# Domino_Di_No_Teardrop.net
KiCad netlist of a schematic drawn in EAGLE
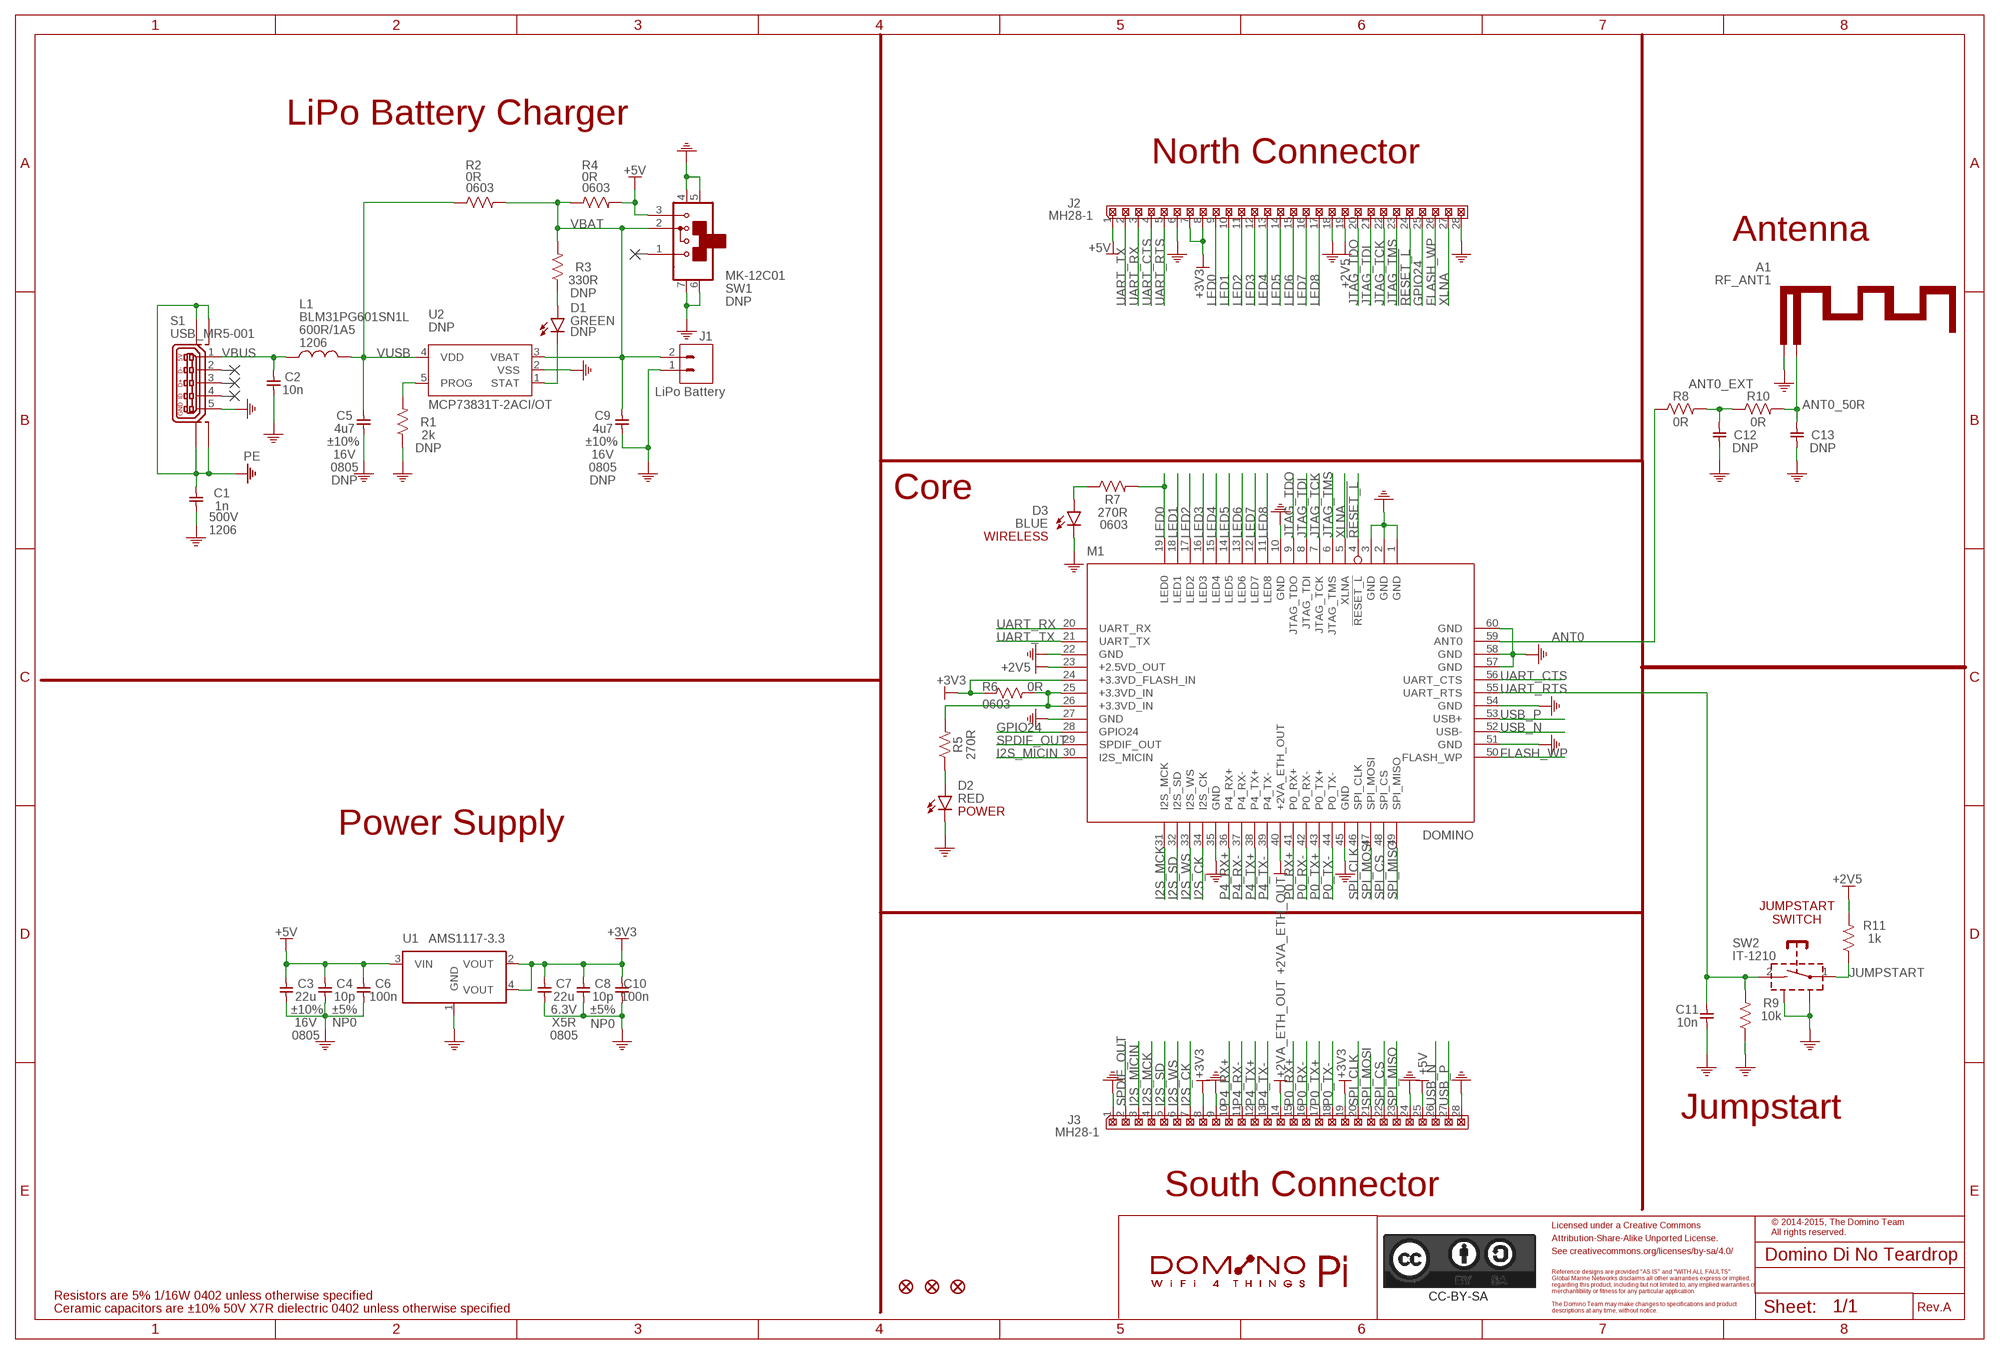
[diagram p0: schematic, sheet 1]

(export (version "E")
  (design (tool "Eeschema 10.0.6"))
  (components
    (comp (ref "A1")
      (value "RF_ANT1")
      (footprint "eagle-import:RF_ANT1")
      (fields (field (name "PARTNO") "WIFI_ANT-2.4GHz"))
      (libsource (lib "eagle-import") (part "RF_ANT1"))
    )
    (comp (ref "C1")
      (value "1n")
      (footprint "eagle-import:C1206")
      (fields
        (field (name "SIZE") "1206")
        (field (name "PARTNO") "C1206_1n_X7R_10%_CER_500V")
        (field (name "VOLT") "500V")
      )
      (libsource (lib "eagle-import") (part "CAP_1206"))
    )
    (comp (ref "C2")
      (value "10n")
      (footprint "eagle-import:C0402")
      (fields (field (name "PARTNO") "C0402_10n_X7R_10%_CER_50V"))
      (libsource (lib "eagle-import") (part "CAP_0402"))
    )
    (comp (ref "C3")
      (value "22u")
      (footprint "eagle-import:C0805")
      (fields
        (field (name "SIZE") "0805")
        (field (name "PARTNO") "C0805_22u_X5R_20%_CER_6V3")
        (field (name "TOL") "±10%")
        (field (name "VOLT") "16V")
      )
      (libsource (lib "eagle-import") (part "CAP_0805"))
    )
    (comp (ref "C4")
      (value "10p")
      (footprint "eagle-import:C0402")
      (fields
        (field (name "PARTNO") "C0402_10p_NP0_5%_CER_50V")
        (field (name "TC") "NP0")
        (field (name "TOL") "±5%")
      )
      (libsource (lib "eagle-import") (part "CAP_0402"))
    )
    (comp (ref "C5")
      (value "4u7")
      (footprint "eagle-import:C0805")
      (fields
        (field (name "SIZE") "0805")
        (field (name "PARTNO") "C0805_4u7_X5R_10%_CER_16V")
        (field (name "TOL") "±10%")
        (field (name "VOLT") "16V")
      )
      (libsource (lib "eagle-import") (part "CAP_0805"))
    )
    (comp (ref "C6")
      (value "100n")
      (footprint "eagle-import:C0402")
      (fields (field (name "PARTNO") "C0402_100n_X7R_10%_CER_50V"))
      (libsource (lib "eagle-import") (part "CAP_0402"))
    )
    (comp (ref "C7")
      (value "22u")
      (footprint "eagle-import:C0805")
      (fields
        (field (name "SIZE") "0805")
        (field (name "PARTNO") "C0805_22u_X5R_20%_CER_6V3")
        (field (name "TC") "X5R")
        (field (name "VOLT") "6.3V")
      )
      (libsource (lib "eagle-import") (part "CAP_0805"))
    )
    (comp (ref "C8")
      (value "10p")
      (footprint "eagle-import:C0402")
      (fields
        (field (name "PARTNO") "C0402_10p_NP0_5%_CER_50V")
        (field (name "TC") "NP0")
        (field (name "TOL") "±5%")
      )
      (libsource (lib "eagle-import") (part "CAP_0402"))
    )
    (comp (ref "C9")
      (value "4u7")
      (footprint "eagle-import:C0805")
      (fields
        (field (name "SIZE") "0805")
        (field (name "PARTNO") "C0805_4u7_X5R_10%_CER_16V")
        (field (name "TOL") "±10%")
        (field (name "VOLT") "16V")
      )
      (libsource (lib "eagle-import") (part "CAP_0805"))
    )
    (comp (ref "C10")
      (value "100n")
      (footprint "eagle-import:C0402")
      (fields (field (name "PARTNO") "C0402_100n_X7R_10%_CER_50V"))
      (libsource (lib "eagle-import") (part "CAP_0402"))
    )
    (comp (ref "C11")
      (value "10n")
      (footprint "eagle-import:C0402")
      (fields (field (name "PARTNO") "C0402_10n_X7R_10%_CER_50V"))
      (libsource (lib "eagle-import") (part "CAP_0402"))
    )
    (comp (ref "C12")
      (value "DNP")
      (footprint "eagle-import:C0402")
      (fields (field (name "PARTNO") "C0402_DNP"))
      (libsource (lib "eagle-import") (part "CAP_0402"))
    )
    (comp (ref "C13")
      (value "DNP")
      (footprint "eagle-import:C0402")
      (fields (field (name "PARTNO") "C0402_DNP"))
      (libsource (lib "eagle-import") (part "CAP_0402"))
    )
    (comp (ref "CC-BY-SA")
      (value "CC-BY-SA_LOGO")
      (footprint "eagle-import:CC-BY-SA_LOGO")
      (libsource (lib "eagle-import") (part "CC-BY-SA_LOGO"))
    )
    (comp (ref "D1")
      (value "GREEN")
      (footprint "eagle-import:LED0402")
      (fields (field (name "PARTNO") "LED0402-GREEN"))
      (libsource (lib "eagle-import") (part "LED_0402"))
    )
    (comp (ref "D2")
      (value "RED")
      (footprint "eagle-import:LED0402")
      (fields (field (name "PARTNO") "LED0402-RED"))
      (libsource (lib "eagle-import") (part "LED_0402"))
    )
    (comp (ref "D3")
      (value "BLUE")
      (footprint "eagle-import:LED0402")
      (fields (field (name "PARTNO") "LED0402-BLUE"))
      (libsource (lib "eagle-import") (part "LED_0402"))
    )
    (comp (ref "F1")
      (value "FIDUCIAL")
      (footprint "eagle-import:FIDUCIAL")
      (libsource (lib "eagle-import") (part "FIDUCIAL"))
    )
    (comp (ref "F2")
      (value "FIDUCIAL")
      (footprint "eagle-import:FIDUCIAL")
      (libsource (lib "eagle-import") (part "FIDUCIAL"))
    )
    (comp (ref "F3")
      (value "FIDUCIAL")
      (footprint "eagle-import:FIDUCIAL")
      (libsource (lib "eagle-import") (part "FIDUCIAL"))
    )
    (comp (ref "J1")
      (value "LiPo Battery")
      (footprint "eagle-import:S2B-PH-SM4-TB")
      (fields (field (name "PARTNO") "S2B-PH-SM4-TB"))
      (libsource (lib "eagle-import") (part "SB-PH-?-TBSM42"))
    )
    (comp (ref "J2")
      (value "MH28-1")
      (footprint "eagle-import:MH28-1-0.1")
      (fields (field (name "PARTNO") "MH28-1-0.1"))
      (libsource (lib "eagle-import") (part "MH28-1"))
    )
    (comp (ref "J3")
      (value "MH28-1")
      (footprint "eagle-import:MH28-1-0.1")
      (fields (field (name "PARTNO") "MH28-1-0.1"))
      (libsource (lib "eagle-import") (part "MH28-1"))
    )
    (comp (ref "L1")
      (value "BLM31PG601SN1L")
      (footprint "eagle-import:FB1206")
      (fields (field (name "SIZE") "1206") (field (name "OPT") "600R/1A5"))
      (libsource (lib "eagle-import") (part "FB_1206"))
    )
    (comp (ref "M1")
      (value "DOMINO")
      (footprint "eagle-import:DOMINO")
      (fields (field (name "PARTNO") "DOMINO-CORE"))
      (libsource (lib "eagle-import") (part "DOMINO"))
    )
    (comp (ref "R1")
      (value "2k")
      (footprint "eagle-import:R0402")
      (fields (field (name "PARTNO") "R0402_2k_5%_62.5mW"))
      (libsource (lib "eagle-import") (part "RES_0402"))
    )
    (comp (ref "R2")
      (value "0R")
      (footprint "eagle-import:R0603")
      (fields (field (name "SIZE") "0603") (field (name "PARTNO") "R0603_0R_5%_125mW"))
      (libsource (lib "eagle-import") (part "RES_0603"))
    )
    (comp (ref "R3")
      (value "330R")
      (footprint "eagle-import:R0402")
      (fields (field (name "PARTNO") "R0402_330R_5%_62.5mW"))
      (libsource (lib "eagle-import") (part "RES_0402"))
    )
    (comp (ref "R4")
      (value "0R")
      (footprint "eagle-import:R0603")
      (fields (field (name "SIZE") "0603") (field (name "PARTNO") "R0603_0R_5%_125mW"))
      (libsource (lib "eagle-import") (part "RES_0603"))
    )
    (comp (ref "R5")
      (value "270R")
      (footprint "eagle-import:R0402")
      (fields (field (name "PARTNO") "R0402_270R_5%_62.5mW"))
      (libsource (lib "eagle-import") (part "RES_0402"))
    )
    (comp (ref "R6")
      (value "0R")
      (footprint "eagle-import:R0603")
      (fields (field (name "SIZE") "0603") (field (name "PARTNO") "R0603_0R_5%_125mW"))
      (libsource (lib "eagle-import") (part "RES_0603"))
    )
    (comp (ref "R7")
      (value "270R")
      (footprint "eagle-import:R0603")
      (fields (field (name "SIZE") "0603") (field (name "PARTNO") "R0603_270R_5%_125mW"))
      (libsource (lib "eagle-import") (part "RES_0603"))
    )
    (comp (ref "R8")
      (value "0R")
      (footprint "eagle-import:R0402")
      (fields (field (name "PARTNO") "R0402_0R_5%_62.5mW"))
      (libsource (lib "eagle-import") (part "RES_0402"))
    )
    (comp (ref "R9")
      (value "10k")
      (footprint "eagle-import:R0402")
      (fields (field (name "PARTNO") "R0402_10k_5%_62.5mW"))
      (libsource (lib "eagle-import") (part "RES_0402"))
    )
    (comp (ref "R10")
      (value "0R")
      (footprint "eagle-import:R0402")
      (fields (field (name "PARTNO") "R0402_0R_5%_62.5mW"))
      (libsource (lib "eagle-import") (part "RES_0402"))
    )
    (comp (ref "R11")
      (value "1k")
      (footprint "eagle-import:R0402")
      (fields (field (name "PARTNO") "R0402_1k_5%_62.5mW"))
      (libsource (lib "eagle-import") (part "RES_0402"))
    )
    (comp (ref "S1")
      (value "USB_MR5-001")
      (footprint "eagle-import:USB-MR5-001")
      (fields (field (name "PARTNO") "USB MR5-001"))
      (libsource (lib "eagle-import") (part "USB_MR5-001"))
    )
    (comp (ref "SW1")
      (value "MK-12C01")
      (footprint "eagle-import:MK-12C01")
      (libsource (lib "eagle-import") (part "MK-12C01"))
    )
    (comp (ref "SW2")
      (value "IT-1210")
      (footprint "eagle-import:IT-1210")
      (libsource (lib "eagle-import") (part "IT-1210"))
    )
    (comp (ref "U1")
      (value "AMS1117-3.3")
      (footprint "eagle-import:SOT223")
      (libsource (lib "eagle-import") (part "AMS1117-3.3"))
    )
    (comp (ref "U2")
      (value "MCP73831T-2ACI/OT")
      (footprint "eagle-import:SOT23-5")
      (libsource (lib "eagle-import") (part "MCP73831T-/OT2ACI"))
    )
    (comp (ref "W1")
      (value "DOMINO_PI_LOGO")
      (footprint "eagle-import:DOMINO_PI_LOGO")
      (libsource (lib "eagle-import") (part "DOMINO_PI_LOGO"))
    )
  )
  (nets
    (net (code "1") (name "+2V5") (class "Default")
      (node (ref "J2") (pin "19") (pinfunction "19_19") (pintype "passive"))
      (node (ref "M1") (pin "23") (pinfunction "+2.5VD_OUT_23") (pintype "power_in"))
      (node (ref "R11") (pin "2") (pinfunction "2_2") (pintype "passive"))
    )
    (net (code "2") (name "+2VA_ETH_OUT") (class "Default")
      (node (ref "J3") (pin "14") (pinfunction "14_14") (pintype "passive"))
      (node (ref "M1") (pin "40") (pinfunction "+2VA_ETH_OUT_40") (pintype "power_in"))
    )
    (net (code "3") (name "+3V3") (class "Default")
      (node (ref "C10") (pin "1") (pinfunction "1_1") (pintype "passive"))
      (node (ref "C7") (pin "1") (pinfunction "1_1") (pintype "passive"))
      (node (ref "C8") (pin "1") (pinfunction "1_1") (pintype "passive"))
      (node (ref "J2") (pin "7") (pinfunction "7_7") (pintype "passive"))
      (node (ref "J2") (pin "8") (pinfunction "8_8") (pintype "passive"))
      (node (ref "J3") (pin "19") (pinfunction "19_19") (pintype "passive"))
      (node (ref "J3") (pin "8") (pinfunction "8_8") (pintype "passive"))
      (node (ref "M1") (pin "24") (pinfunction "+3.3VD_FLASH_IN_24") (pintype "power_in"))
      (node (ref "R6") (pin "1") (pinfunction "1_1") (pintype "passive"))
      (node (ref "U1") (pin "2") (pinfunction "VOUT_2") (pintype "power_in"))
      (node (ref "U1") (pin "4") (pinfunction "VOUT_4") (pintype "bidirectional"))
    )
    (net (code "4") (name "+5V") (class "Default")
      (node (ref "C3") (pin "1") (pinfunction "1_1") (pintype "passive"))
      (node (ref "C4") (pin "1") (pinfunction "1_1") (pintype "passive"))
      (node (ref "C6") (pin "1") (pinfunction "1_1") (pintype "passive"))
      (node (ref "J2") (pin "1") (pinfunction "1_1") (pintype "passive"))
      (node (ref "J3") (pin "25") (pinfunction "25_25") (pintype "passive"))
      (node (ref "R4") (pin "2") (pinfunction "2_2") (pintype "passive"))
      (node (ref "SW1") (pin "3") (pinfunction "3_3") (pintype "passive"))
      (node (ref "U1") (pin "3") (pinfunction "VIN_3") (pintype "power_in"))
    )
    (net (code "5") (name "/ANT0") (class "Default")
      (node (ref "M1") (pin "59") (pinfunction "ANT0_59") (pintype "passive"))
      (node (ref "R8") (pin "1") (pinfunction "1_1") (pintype "passive"))
    )
    (net (code "6") (name "/ANT0_50R") (class "Default")
      (node (ref "A1") (pin "FEED") (pinfunction "FEED_FEED") (pintype "passive"))
      (node (ref "C13") (pin "1") (pinfunction "1_1") (pintype "passive"))
      (node (ref "R10") (pin "2") (pinfunction "2_2") (pintype "passive"))
    )
    (net (code "7") (name "/ANT0_EXT") (class "Default")
      (node (ref "C12") (pin "1") (pinfunction "1_1") (pintype "passive"))
      (node (ref "R10") (pin "1") (pinfunction "1_1") (pintype "passive"))
      (node (ref "R8") (pin "2") (pinfunction "2_2") (pintype "passive"))
    )
    (net (code "8") (name "/FLASH_WP") (class "Default")
      (node (ref "J2") (pin "26") (pinfunction "26_26") (pintype "passive"))
      (node (ref "M1") (pin "50") (pinfunction "FLASH_WP_50") (pintype "bidirectional"))
    )
    (net (code "9") (name "/GPIO24") (class "Default")
      (node (ref "J2") (pin "25") (pinfunction "25_25") (pintype "passive"))
      (node (ref "M1") (pin "28") (pinfunction "GPIO24_28") (pintype "bidirectional"))
    )
    (net (code "10") (name "/I2S_CK") (class "Default")
      (node (ref "J3") (pin "7") (pinfunction "7_7") (pintype "passive"))
      (node (ref "M1") (pin "34") (pinfunction "I2S_CK_34") (pintype "bidirectional"))
    )
    (net (code "11") (name "/I2S_MCK") (class "Default")
      (node (ref "J3") (pin "4") (pinfunction "4_4") (pintype "passive"))
      (node (ref "M1") (pin "31") (pinfunction "I2S_MCK_31") (pintype "bidirectional"))
    )
    (net (code "12") (name "/I2S_MICIN") (class "Default")
      (node (ref "J3") (pin "3") (pinfunction "3_3") (pintype "passive"))
      (node (ref "M1") (pin "30") (pinfunction "I2S_MICIN_30") (pintype "bidirectional"))
    )
    (net (code "13") (name "/I2S_SD") (class "Default")
      (node (ref "J3") (pin "5") (pinfunction "5_5") (pintype "passive"))
      (node (ref "M1") (pin "32") (pinfunction "I2S_SD_32") (pintype "bidirectional"))
    )
    (net (code "14") (name "/I2S_WS") (class "Default")
      (node (ref "J3") (pin "6") (pinfunction "6_6") (pintype "passive"))
      (node (ref "M1") (pin "33") (pinfunction "I2S_WS_33") (pintype "bidirectional"))
    )
    (net (code "15") (name "/JTAG_TCK") (class "Default")
      (node (ref "J2") (pin "22") (pinfunction "22_22") (pintype "passive"))
      (node (ref "M1") (pin "7") (pinfunction "JTAG_TCK_7") (pintype "bidirectional"))
    )
    (net (code "16") (name "/JTAG_TDI") (class "Default")
      (node (ref "J2") (pin "21") (pinfunction "21_21") (pintype "passive"))
      (node (ref "M1") (pin "8") (pinfunction "JTAG_TDI_8") (pintype "bidirectional"))
    )
    (net (code "17") (name "/JTAG_TDO") (class "Default")
      (node (ref "J2") (pin "20") (pinfunction "20_20") (pintype "passive"))
      (node (ref "M1") (pin "9") (pinfunction "JTAG_TDO_9") (pintype "bidirectional"))
    )
    (net (code "18") (name "/JTAG_TMS") (class "Default")
      (node (ref "J2") (pin "23") (pinfunction "23_23") (pintype "passive"))
      (node (ref "M1") (pin "6") (pinfunction "JTAG_TMS_6") (pintype "bidirectional"))
    )
    (net (code "19") (name "/JUMPSTART") (class "Default")
      (node (ref "R11") (pin "1") (pinfunction "1_1") (pintype "passive"))
      (node (ref "SW2") (pin "1") (pinfunction "1_1") (pintype "passive"))
    )
    (net (code "20") (name "/LED0") (class "Default")
      (node (ref "J2") (pin "9") (pinfunction "9_9") (pintype "passive"))
      (node (ref "M1") (pin "19") (pinfunction "LED0_19") (pintype "bidirectional"))
      (node (ref "R7") (pin "2") (pinfunction "2_2") (pintype "passive"))
    )
    (net (code "21") (name "/LED1") (class "Default")
      (node (ref "J2") (pin "10") (pinfunction "10_10") (pintype "passive"))
      (node (ref "M1") (pin "18") (pinfunction "LED1_18") (pintype "bidirectional"))
    )
    (net (code "22") (name "/LED2") (class "Default")
      (node (ref "J2") (pin "11") (pinfunction "11_11") (pintype "passive"))
      (node (ref "M1") (pin "17") (pinfunction "LED2_17") (pintype "bidirectional"))
    )
    (net (code "23") (name "/LED3") (class "Default")
      (node (ref "J2") (pin "12") (pinfunction "12_12") (pintype "passive"))
      (node (ref "M1") (pin "16") (pinfunction "LED3_16") (pintype "bidirectional"))
    )
    (net (code "24") (name "/LED4") (class "Default")
      (node (ref "J2") (pin "13") (pinfunction "13_13") (pintype "passive"))
      (node (ref "M1") (pin "15") (pinfunction "LED4_15") (pintype "bidirectional"))
    )
    (net (code "25") (name "/LED5") (class "Default")
      (node (ref "J2") (pin "14") (pinfunction "14_14") (pintype "passive"))
      (node (ref "M1") (pin "14") (pinfunction "LED5_14") (pintype "bidirectional"))
    )
    (net (code "26") (name "/LED6") (class "Default")
      (node (ref "J2") (pin "15") (pinfunction "15_15") (pintype "passive"))
      (node (ref "M1") (pin "13") (pinfunction "LED6_13") (pintype "bidirectional"))
    )
    (net (code "27") (name "/LED7") (class "Default")
      (node (ref "J2") (pin "16") (pinfunction "16_16") (pintype "passive"))
      (node (ref "M1") (pin "12") (pinfunction "LED7_12") (pintype "bidirectional"))
    )
    (net (code "28") (name "/LED8") (class "Default")
      (node (ref "J2") (pin "17") (pinfunction "17_17") (pintype "passive"))
      (node (ref "M1") (pin "11") (pinfunction "LED8_11") (pintype "bidirectional"))
    )
    (net (code "29") (name "/P0_RX+") (class "Default")
      (node (ref "J3") (pin "15") (pinfunction "15_15") (pintype "passive"))
      (node (ref "M1") (pin "41") (pinfunction "P0_RX+_41") (pintype "passive"))
    )
    (net (code "30") (name "/P0_RX-") (class "Default")
      (node (ref "J3") (pin "16") (pinfunction "16_16") (pintype "passive"))
      (node (ref "M1") (pin "42") (pinfunction "P0_RX-_42") (pintype "passive"))
    )
    (net (code "31") (name "/P0_TX+") (class "Default")
      (node (ref "J3") (pin "17") (pinfunction "17_17") (pintype "passive"))
      (node (ref "M1") (pin "43") (pinfunction "P0_TX+_43") (pintype "passive"))
    )
    (net (code "32") (name "/P0_TX-") (class "Default")
      (node (ref "J3") (pin "18") (pinfunction "18_18") (pintype "passive"))
      (node (ref "M1") (pin "44") (pinfunction "P0_TX-_44") (pintype "passive"))
    )
    (net (code "33") (name "/P4_RX+") (class "Default")
      (node (ref "J3") (pin "10") (pinfunction "10_10") (pintype "passive"))
      (node (ref "M1") (pin "36") (pinfunction "P4_RX+_36") (pintype "passive"))
    )
    (net (code "34") (name "/P4_RX-") (class "Default")
      (node (ref "J3") (pin "11") (pinfunction "11_11") (pintype "passive"))
      (node (ref "M1") (pin "37") (pinfunction "P4_RX-_37") (pintype "passive"))
    )
    (net (code "35") (name "/P4_TX+") (class "Default")
      (node (ref "J3") (pin "12") (pinfunction "12_12") (pintype "passive"))
      (node (ref "M1") (pin "38") (pinfunction "P4_TX+_38") (pintype "passive"))
    )
    (net (code "36") (name "/P4_TX-") (class "Default")
      (node (ref "J3") (pin "13") (pinfunction "13_13") (pintype "passive"))
      (node (ref "M1") (pin "39") (pinfunction "P4_TX-_39") (pintype "passive"))
    )
    (net (code "37") (name "/SPDIF_OUT") (class "Default")
      (node (ref "J3") (pin "2") (pinfunction "2_2") (pintype "passive"))
      (node (ref "M1") (pin "29") (pinfunction "SPDIF_OUT_29") (pintype "bidirectional"))
    )
    (net (code "38") (name "/SPI_CLK") (class "Default")
      (node (ref "J3") (pin "20") (pinfunction "20_20") (pintype "passive"))
      (node (ref "M1") (pin "46") (pinfunction "SPI_CLK_46") (pintype "bidirectional"))
    )
    (net (code "39") (name "/SPI_CS") (class "Default")
      (node (ref "J3") (pin "22") (pinfunction "22_22") (pintype "passive"))
      (node (ref "M1") (pin "48") (pinfunction "SPI_CS_48") (pintype "bidirectional"))
    )
    (net (code "40") (name "/SPI_MISO") (class "Default")
      (node (ref "J3") (pin "23") (pinfunction "23_23") (pintype "passive"))
      (node (ref "M1") (pin "49") (pinfunction "SPI_MISO_49") (pintype "bidirectional"))
    )
    (net (code "41") (name "/SPI_MOSI") (class "Default")
      (node (ref "J3") (pin "21") (pinfunction "21_21") (pintype "passive"))
      (node (ref "M1") (pin "47") (pinfunction "SPI_MOSI_47") (pintype "bidirectional"))
    )
    (net (code "42") (name "/UART_CTS") (class "Default")
      (node (ref "J2") (pin "4") (pinfunction "4_4") (pintype "passive"))
      (node (ref "M1") (pin "56") (pinfunction "UART_CTS_56") (pintype "bidirectional"))
    )
    (net (code "43") (name "/UART_RTS") (class "Default")
      (node (ref "C11") (pin "1") (pinfunction "1_1") (pintype "passive"))
      (node (ref "J2") (pin "5") (pinfunction "5_5") (pintype "passive"))
      (node (ref "M1") (pin "55") (pinfunction "UART_RTS_55") (pintype "bidirectional"))
      (node (ref "R9") (pin "2") (pinfunction "2_2") (pintype "passive"))
      (node (ref "SW2") (pin "2") (pinfunction "2_2") (pintype "passive"))
    )
    (net (code "44") (name "/UART_RX") (class "Default")
      (node (ref "J2") (pin "3") (pinfunction "3_3") (pintype "passive"))
      (node (ref "M1") (pin "20") (pinfunction "UART_RX_20") (pintype "bidirectional"))
    )
    (net (code "45") (name "/UART_TX") (class "Default")
      (node (ref "J2") (pin "2") (pinfunction "2_2") (pintype "passive"))
      (node (ref "M1") (pin "21") (pinfunction "UART_TX_21") (pintype "bidirectional"))
    )
    (net (code "46") (name "/USB_N") (class "Default")
      (node (ref "J3") (pin "26") (pinfunction "26_26") (pintype "passive"))
      (node (ref "M1") (pin "52") (pinfunction "USB-_52") (pintype "passive"))
    )
    (net (code "47") (name "/USB_P") (class "Default")
      (node (ref "J3") (pin "27") (pinfunction "27_27") (pintype "passive"))
      (node (ref "M1") (pin "53") (pinfunction "USB+_53") (pintype "passive"))
    )
    (net (code "48") (name "/VBAT") (class "Default")
      (node (ref "C9") (pin "1") (pinfunction "1_1") (pintype "passive"))
      (node (ref "J1") (pin "2") (pinfunction "2_2") (pintype "passive"))
      (node (ref "R2") (pin "2") (pinfunction "2_2") (pintype "passive"))
      (node (ref "R3") (pin "2") (pinfunction "2_2") (pintype "passive"))
      (node (ref "R4") (pin "1") (pinfunction "1_1") (pintype "passive"))
      (node (ref "SW1") (pin "2") (pinfunction "2_2") (pintype "passive"))
      (node (ref "U2") (pin "3") (pinfunction "VBAT_3") (pintype "power_in"))
    )
    (net (code "49") (name "/VBUS") (class "Default")
      (node (ref "C2") (pin "1") (pinfunction "1_1") (pintype "passive"))
      (node (ref "L1") (pin "2") (pinfunction "2_2") (pintype "passive"))
      (node (ref "S1") (pin "1") (pinfunction "1_1") (pintype "passive"))
    )
    (net (code "50") (name "/VUSB") (class "Default")
      (node (ref "C5") (pin "1") (pinfunction "1_1") (pintype "passive"))
      (node (ref "L1") (pin "1") (pinfunction "1_1") (pintype "passive"))
      (node (ref "R2") (pin "1") (pinfunction "1_1") (pintype "passive"))
      (node (ref "U2") (pin "4") (pinfunction "VDD_4") (pintype "power_in"))
    )
    (net (code "51") (name "/XLNA") (class "Default")
      (node (ref "J2") (pin "27") (pinfunction "27_27") (pintype "passive"))
      (node (ref "M1") (pin "5") (pinfunction "XLNA_5") (pintype "bidirectional"))
    )
    (net (code "52") (name "/~{RESET_L}") (class "Default")
      (node (ref "J2") (pin "24") (pinfunction "24_24") (pintype "passive"))
      (node (ref "M1") (pin "4") (pinfunction "~{RESET_L}_4") (pintype "input"))
    )
    (net (code "53") (name "GND") (class "Default")
      (node (ref "A1") (pin "GND") (pinfunction "GND_GND") (pintype "power_in"))
      (node (ref "C1") (pin "2") (pinfunction "2_2") (pintype "passive"))
      (node (ref "C10") (pin "2") (pinfunction "2_2") (pintype "passive"))
      (node (ref "C11") (pin "2") (pinfunction "2_2") (pintype "passive"))
      (node (ref "C12") (pin "2") (pinfunction "2_2") (pintype "passive"))
      (node (ref "C13") (pin "2") (pinfunction "2_2") (pintype "passive"))
      (node (ref "C2") (pin "2") (pinfunction "2_2") (pintype "passive"))
      (node (ref "C3") (pin "2") (pinfunction "2_2") (pintype "passive"))
      (node (ref "C4") (pin "2") (pinfunction "2_2") (pintype "passive"))
      (node (ref "C5") (pin "2") (pinfunction "2_2") (pintype "passive"))
      (node (ref "C6") (pin "2") (pinfunction "2_2") (pintype "passive"))
      (node (ref "C7") (pin "2") (pinfunction "2_2") (pintype "passive"))
      (node (ref "C8") (pin "2") (pinfunction "2_2") (pintype "passive"))
      (node (ref "C9") (pin "2") (pinfunction "2_2") (pintype "passive"))
      (node (ref "D2") (pin "1") (pinfunction "C_1") (pintype "passive"))
      (node (ref "D3") (pin "1") (pinfunction "C_1") (pintype "passive"))
      (node (ref "J1") (pin "1") (pinfunction "1_1") (pintype "passive"))
      (node (ref "J2") (pin "18") (pinfunction "18_18") (pintype "passive"))
      (node (ref "J2") (pin "28") (pinfunction "28_28") (pintype "passive"))
      (node (ref "J2") (pin "6") (pinfunction "6_6") (pintype "passive"))
      (node (ref "J3") (pin "1") (pinfunction "1_1") (pintype "passive"))
      (node (ref "J3") (pin "24") (pinfunction "24_24") (pintype "passive"))
      (node (ref "J3") (pin "28") (pinfunction "28_28") (pintype "passive"))
      (node (ref "J3") (pin "9") (pinfunction "9_9") (pintype "passive"))
      (node (ref "M1") (pin "1") (pinfunction "GND_1") (pintype "power_in"))
      (node (ref "M1") (pin "10") (pinfunction "GND_10") (pintype "power_in"))
      (node (ref "M1") (pin "2") (pinfunction "GND_2") (pintype "power_in"))
      (node (ref "M1") (pin "22") (pinfunction "GND_22") (pintype "power_in"))
      (node (ref "M1") (pin "27") (pinfunction "GND_27") (pintype "power_in"))
      (node (ref "M1") (pin "3") (pinfunction "GND_3") (pintype "power_in"))
      (node (ref "M1") (pin "35") (pinfunction "GND_35") (pintype "power_in"))
      (node (ref "M1") (pin "45") (pinfunction "GND_45") (pintype "power_in"))
      (node (ref "M1") (pin "51") (pinfunction "GND_51") (pintype "power_in"))
      (node (ref "M1") (pin "54") (pinfunction "GND_54") (pintype "power_in"))
      (node (ref "M1") (pin "57") (pinfunction "GND_57") (pintype "power_in"))
      (node (ref "M1") (pin "58") (pinfunction "GND_58") (pintype "power_in"))
      (node (ref "M1") (pin "60") (pinfunction "GND_60") (pintype "power_in"))
      (node (ref "R1") (pin "1") (pinfunction "1_1") (pintype "passive"))
      (node (ref "R9") (pin "1") (pinfunction "1_1") (pintype "passive"))
      (node (ref "S1") (pin "5") (pinfunction "5_5") (pintype "passive"))
      (node (ref "SW1") (pin "4") (pinfunction "4_4") (pintype "passive"))
      (node (ref "SW1") (pin "5") (pinfunction "5_5") (pintype "passive"))
      (node (ref "SW1") (pin "6") (pinfunction "6_6") (pintype "passive"))
      (node (ref "SW1") (pin "7") (pinfunction "7_7") (pintype "passive"))
      (node (ref "SW2") (pin "SH$1") (pinfunction "SH$1_SH$1") (pintype "passive"))
      (node (ref "SW2") (pin "SH$2") (pinfunction "SH$2_SH$2") (pintype "passive"))
      (node (ref "U1") (pin "1") (pinfunction "GND_1") (pintype "power_in"))
      (node (ref "U2") (pin "2") (pinfunction "VSS_2") (pintype "power_in"))
    )
    (net (code "54") (name "Net-(D1-A)") (class "Default")
      (node (ref "D1") (pin "2") (pinfunction "A_2") (pintype "passive"))
      (node (ref "R3") (pin "1") (pinfunction "1_1") (pintype "passive"))
    )
    (net (code "55") (name "Net-(D1-C)") (class "Default")
      (node (ref "D1") (pin "1") (pinfunction "C_1") (pintype "passive"))
      (node (ref "U2") (pin "1") (pinfunction "STAT_1") (pintype "output"))
    )
    (net (code "56") (name "Net-(D2-A)") (class "Default")
      (node (ref "D2") (pin "2") (pinfunction "A_2") (pintype "passive"))
      (node (ref "R5") (pin "1") (pinfunction "1_1") (pintype "passive"))
    )
    (net (code "57") (name "Net-(D3-A)") (class "Default")
      (node (ref "D3") (pin "2") (pinfunction "A_2") (pintype "passive"))
      (node (ref "R7") (pin "1") (pinfunction "1_1") (pintype "passive"))
    )
    (net (code "58") (name "Net-(M1-+3.3VD_IN-Pad25)") (class "Default")
      (node (ref "M1") (pin "25") (pinfunction "+3.3VD_IN_25") (pintype "power_in"))
      (node (ref "M1") (pin "26") (pinfunction "+3.3VD_IN_26") (pintype "power_in"))
      (node (ref "R5") (pin "2") (pinfunction "2_2") (pintype "passive"))
      (node (ref "R6") (pin "2") (pinfunction "2_2") (pintype "passive"))
    )
    (net (code "59") (name "Net-(U2-PROG)") (class "Default")
      (node (ref "R1") (pin "2") (pinfunction "2_2") (pintype "passive"))
      (node (ref "U2") (pin "5") (pinfunction "PROG_5") (pintype "passive"))
    )
    (net (code "60") (name "PE") (class "Default")
      (node (ref "C1") (pin "1") (pinfunction "1_1") (pintype "passive"))
      (node (ref "S1") (pin "SH$1") (pinfunction "M0_SH$1") (pintype "passive"))
      (node (ref "S1") (pin "SH$2") (pinfunction "M1_SH$2") (pintype "passive"))
      (node (ref "S1") (pin "SH$3") (pinfunction "M2_SH$3") (pintype "passive"))
      (node (ref "S1") (pin "SH$4") (pinfunction "M3_SH$4") (pintype "passive"))
    )
    (net (code "61") (name "unconnected-(S1-Pad2)") (class "Default")
      (node (ref "S1") (pin "2") (pinfunction "2_2") (pintype "passive"))
    )
    (net (code "62") (name "unconnected-(S1-Pad3)") (class "Default")
      (node (ref "S1") (pin "3") (pinfunction "3_3") (pintype "passive"))
    )
    (net (code "63") (name "unconnected-(S1-Pad4)") (class "Default")
      (node (ref "S1") (pin "4") (pinfunction "4_4") (pintype "passive"))
    )
    (net (code "64") (name "unconnected-(SW1-Pad1)") (class "Default")
      (node (ref "SW1") (pin "1") (pinfunction "1_1") (pintype "passive"))
    )
  )
)
